# WIFI.net
KiCad netlist of a schematic drawn in Altium Designer
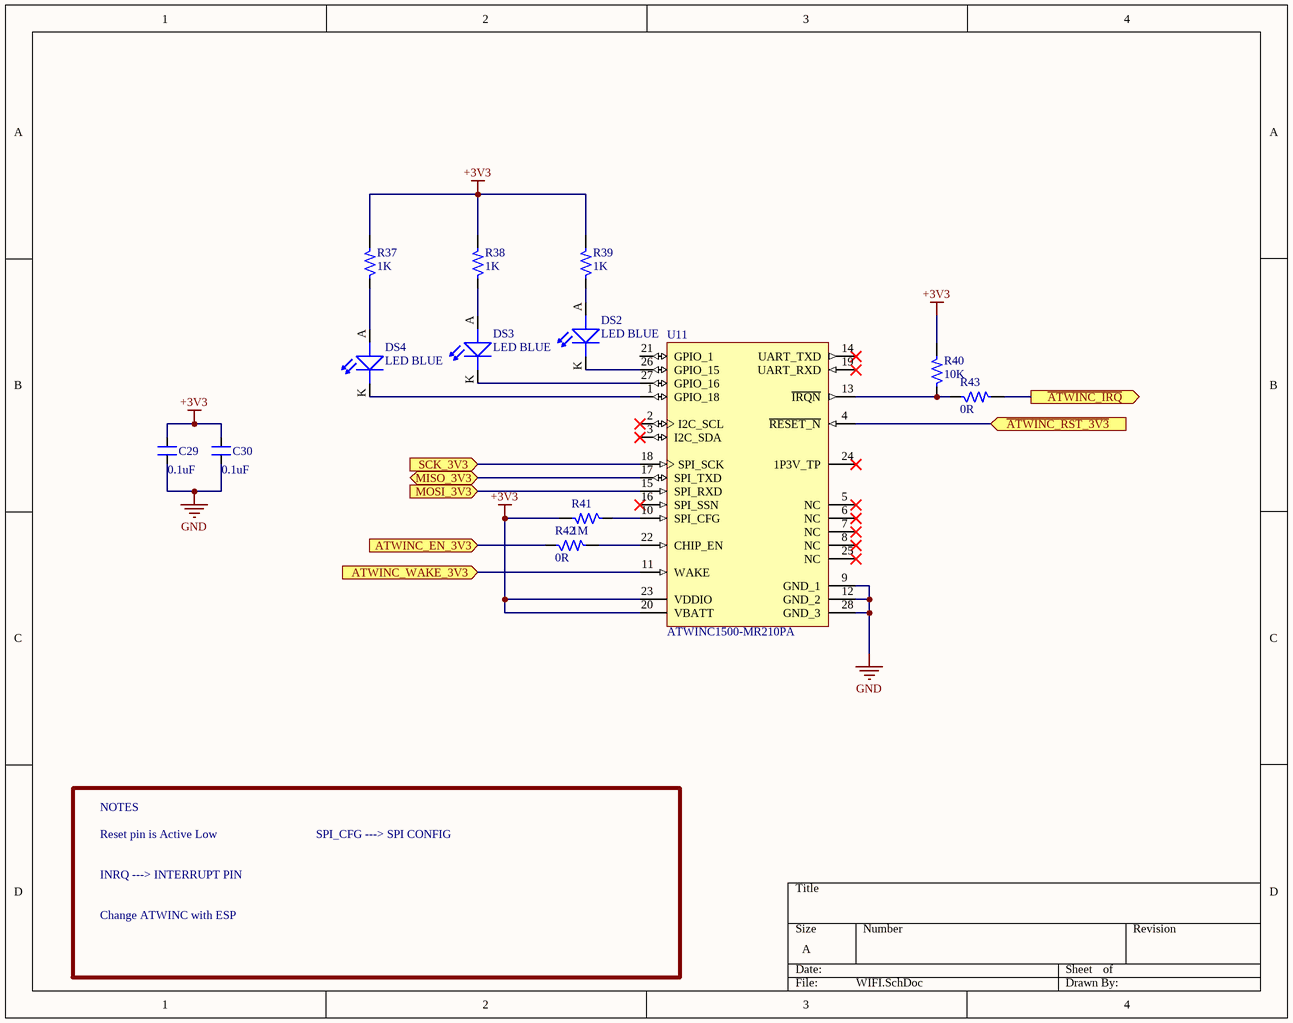
[diagram p0: WIFI.SchDoc]

(export (version "E")
  (design (tool "Eeschema 10.0.6"))
  (components
    (comp (ref "C29")
      (value "0.1uF")
      (footprint "CAP_0805")
      (description "0.1µF ±5% 50V Ceramic Capacitor X7R 0805 (2012 Metric)")
      (fields
        (field (name "MANUFACTURER") "AVX Corporation")
        (field (name "MANUFACTURER PART NUMBER") "08055C104JAT4A")
      )
      (libsource (lib "ESTEEMPCBLIB") (part "CAP_0.1uF-50V-5%-0805"))
    )
    (comp (ref "C30")
      (value "0.1uF")
      (footprint "CAP_0805")
      (description "0.1µF ±5% 50V Ceramic Capacitor X7R 0805 (2012 Metric)")
      (fields
        (field (name "MANUFACTURER") "AVX Corporation")
        (field (name "MANUFACTURER PART NUMBER") "08055C104JAT4A")
      )
      (libsource (lib "ESTEEMPCBLIB") (part "CAP_0.1uF-50V-5%-0805"))
    )
    (comp (ref "DS2")
      (value "LED BLUE")
      (footprint "LED_0805")
      (description "Blue 470nm LED Indication - Discrete 3.3V 0805 (2012 Metric)")
      (fields
        (field (name "MANUFACTURER") "Vishay Lite-On")
        (field (name "MANUFACTURER PART NUMBER") "LTST-C171TBKT")
      )
      (libsource (lib "ESTEEMPCBLIB") (part "LED_BLUE-3V3-20mA-0805"))
    )
    (comp (ref "DS3")
      (value "LED BLUE")
      (footprint "LED_0805")
      (description "Blue 470nm LED Indication - Discrete 3.3V 0805 (2012 Metric)")
      (fields
        (field (name "MANUFACTURER") "Vishay Lite-On")
        (field (name "MANUFACTURER PART NUMBER") "LTST-C171TBKT")
      )
      (libsource (lib "ESTEEMPCBLIB") (part "LED_BLUE-3V3-20mA-0805"))
    )
    (comp (ref "DS4")
      (value "LED BLUE")
      (footprint "LED_0805")
      (description "Blue 470nm LED Indication - Discrete 3.3V 0805 (2012 Metric)")
      (fields
        (field (name "MANUFACTURER") "Vishay Lite-On")
        (field (name "MANUFACTURER PART NUMBER") "LTST-C171TBKT")
      )
      (libsource (lib "ESTEEMPCBLIB") (part "LED_BLUE-3V3-20mA-0805"))
    )
    (comp (ref "R37")
      (value "1K")
      (footprint "RES_0805")
      (description "1 kOhms ±1% 0.125W, 1/8W Chip Resistor 0805 (2012 Metric) Moisture Resistant Thick Film")
      (fields (field (name "MANUFACTURER") "Walsin") (field (name "MANUFACTURER PART NUMBER") "WR08X1001FTL"))
      (libsource (lib "ESTEEMPCBLIB") (part "RES_1K-0.125W-1%-0805"))
    )
    (comp (ref "R38")
      (value "1K")
      (footprint "RES_0805")
      (description "1 kOhms ±1% 0.125W, 1/8W Chip Resistor 0805 (2012 Metric) Moisture Resistant Thick Film")
      (fields (field (name "MANUFACTURER") "Walsin") (field (name "MANUFACTURER PART NUMBER") "WR08X1001FTL"))
      (libsource (lib "ESTEEMPCBLIB") (part "RES_1K-0.125W-1%-0805"))
    )
    (comp (ref "R39")
      (value "1K")
      (footprint "RES_0805")
      (description "1 kOhms ±1% 0.125W, 1/8W Chip Resistor 0805 (2012 Metric) Moisture Resistant Thick Film")
      (fields (field (name "MANUFACTURER") "Walsin") (field (name "MANUFACTURER PART NUMBER") "WR08X1001FTL"))
      (libsource (lib "ESTEEMPCBLIB") (part "RES_1K-0.125W-1%-0805"))
    )
    (comp (ref "R40")
      (value "10K")
      (footprint "RES_0805")
      (description "10 kOhms ±1% 0.125W, 1/8W Chip Resistor 0805 (2012 Metric) Automotive AEC-Q200 Thick Film")
      (fields (field (name "MANUFACTURER") "CTS") (field (name "MANUFACTURER PART NUMBER") "WR08X1002FTL"))
      (libsource (lib "ESTEEMPCBLIB") (part "RES_10K-0.125W-1%-0805"))
    )
    (comp (ref "R41")
      (value "1M")
      (footprint "RES_0805")
      (description "1 MOhms ±1% 0.125W, 1/8W Chip Resistor 0805 (2012 Metric) Automotive AEC-Q200 Thick Film")
      (fields (field (name "MANUFACTURER") "Walsin") (field (name "MANUFACTURER PART NUMBER") "WR08X1004FTL"))
      (libsource (lib "ESTEEMPCBLIB") (part "RES_1M-0.125W-1%-0805"))
    )
    (comp (ref "R42")
      (value "0R")
      (footprint "RES_0805")
      (description "0 Ohms Jumper 0.125W, 1/8W Chip Resistor 0805 (2012 Metric) Automotive AEC-Q200 Thick Film")
      (fields (field (name "MANUFACTURER") "Walsin") (field (name "MANUFACTURER PART NUMBER") "WR08X000PTL"))
      (libsource (lib "ESTEEMPCBLIB") (part "RES_0R-0.125W-1%-0805"))
    )
    (comp (ref "R43")
      (value "0R")
      (footprint "RES_0805")
      (description "0 Ohms Jumper 0.125W, 1/8W Chip Resistor 0805 (2012 Metric) Automotive AEC-Q200 Thick Film")
      (fields (field (name "MANUFACTURER") "Walsin") (field (name "MANUFACTURER PART NUMBER") "WR08X000PTL"))
      (libsource (lib "ESTEEMPCBLIB") (part "RES_0R-0.125W-1%-0805"))
    )
    (comp (ref "U11")
      (value "ATWINC1500-MR210PA")
      (footprint "ATML-ATWINC1500-MR210PA-28_V")
      (description "IEEE 802.11 b/g/n IoT Module, 2.4 GHz, 2.7 to 3.6 V, -40 to 85 degC, 28-Pin Module, RoHS, Tray")
      (fields (field (name "GENERIC PART NUMBER") "ATWINC1500"))
      (libsource (lib "TAREKPCBLIB") (part "ATWINC1500-MR210PA"))
    )
  )
  (nets
    (net (code "1") (name "+3V3") (class "Default")
      (node (ref "C29") (pin "2") (pinfunction "2_2") (pintype "passive"))
      (node (ref "C30") (pin "2") (pinfunction "2_2") (pintype "passive"))
      (node (ref "R37") (pin "2") (pinfunction "2_2") (pintype "passive"))
      (node (ref "R38") (pin "2") (pinfunction "2_2") (pintype "passive"))
      (node (ref "R39") (pin "2") (pinfunction "2_2") (pintype "passive"))
      (node (ref "R40") (pin "2") (pinfunction "2_2") (pintype "passive"))
      (node (ref "R41") (pin "2") (pinfunction "2_2") (pintype "passive"))
      (node (ref "U11") (pin "20") (pinfunction "VBATT_20") (pintype "power_in"))
      (node (ref "U11") (pin "23") (pinfunction "VDDIO_23") (pintype "power_in"))
    )
    (net (code "2") (name "/ATWINC_EN_3V3") (class "Default")
      (node (ref "R42") (pin "1") (pinfunction "1_1") (pintype "passive"))
    )
    (net (code "3") (name "/ATWINC_IRQ") (class "Default")
      (node (ref "R43") (pin "2") (pinfunction "2_2") (pintype "passive"))
    )
    (net (code "4") (name "/ATWINC_RST_3V3") (class "Default")
      (node (ref "U11") (pin "4") (pinfunction "RESET_N_4") (pintype "input"))
    )
    (net (code "5") (name "/ATWINC_WAKE_3V3") (class "Default")
      (node (ref "U11") (pin "11") (pinfunction "WAKE_11") (pintype "input"))
    )
    (net (code "6") (name "/MISO_3V3") (class "Default")
      (node (ref "U11") (pin "17") (pinfunction "SPI_TXD_17") (pintype "bidirectional"))
    )
    (net (code "7") (name "/MOSI_3V3") (class "Default")
      (node (ref "U11") (pin "15") (pinfunction "SPI_RXD_15") (pintype "input"))
    )
    (net (code "8") (name "/SCK_3V3") (class "Default")
      (node (ref "U11") (pin "18") (pinfunction "SPI_SCK_18") (pintype "input"))
    )
    (net (code "9") (name "GND") (class "Default")
      (node (ref "C29") (pin "1") (pinfunction "1_1") (pintype "passive"))
      (node (ref "C30") (pin "1") (pinfunction "1_1") (pintype "passive"))
      (node (ref "U11") (pin "12") (pinfunction "GND_2_12") (pintype "power_in"))
      (node (ref "U11") (pin "28") (pinfunction "GND_3_28") (pintype "power_in"))
      (node (ref "U11") (pin "9") (pinfunction "GND_1_9") (pintype "power_in"))
    )
    (net (code "10") (name "Net-(DS2-ANODE)") (class "Default")
      (node (ref "DS2") (pin "A") (pinfunction "ANODE_A") (pintype "passive"))
      (node (ref "R39") (pin "1") (pinfunction "1_1") (pintype "passive"))
    )
    (net (code "11") (name "Net-(DS2-CATHODE)") (class "Default")
      (node (ref "DS2") (pin "K") (pinfunction "CATHODE_K") (pintype "passive"))
      (node (ref "U11") (pin "26") (pinfunction "GPIO_15_26") (pintype "bidirectional"))
    )
    (net (code "12") (name "Net-(DS3-ANODE)") (class "Default")
      (node (ref "DS3") (pin "A") (pinfunction "ANODE_A") (pintype "passive"))
      (node (ref "R38") (pin "1") (pinfunction "1_1") (pintype "passive"))
    )
    (net (code "13") (name "Net-(DS3-CATHODE)") (class "Default")
      (node (ref "DS3") (pin "K") (pinfunction "CATHODE_K") (pintype "passive"))
      (node (ref "U11") (pin "27") (pinfunction "GPIO_16_27") (pintype "bidirectional"))
    )
    (net (code "14") (name "Net-(DS4-ANODE)") (class "Default")
      (node (ref "DS4") (pin "A") (pinfunction "ANODE_A") (pintype "passive"))
      (node (ref "R37") (pin "1") (pinfunction "1_1") (pintype "passive"))
    )
    (net (code "15") (name "Net-(DS4-CATHODE)") (class "Default")
      (node (ref "DS4") (pin "K") (pinfunction "CATHODE_K") (pintype "passive"))
      (node (ref "U11") (pin "1") (pinfunction "GPIO_18_1") (pintype "bidirectional"))
    )
    (net (code "16") (name "Net-(U11-CHIP_EN)") (class "Default")
      (node (ref "R42") (pin "2") (pinfunction "2_2") (pintype "passive"))
      (node (ref "U11") (pin "22") (pinfunction "CHIP_EN_22") (pintype "input"))
    )
    (net (code "17") (name "Net-(U11-IRQN)") (class "Default")
      (node (ref "R40") (pin "1") (pinfunction "1_1") (pintype "passive"))
      (node (ref "R43") (pin "1") (pinfunction "1_1") (pintype "passive"))
      (node (ref "U11") (pin "13") (pinfunction "IRQN_13") (pintype "output"))
    )
    (net (code "18") (name "Net-(U11-SPI_CFG)") (class "Default")
      (node (ref "R41") (pin "1") (pinfunction "1_1") (pintype "passive"))
      (node (ref "U11") (pin "10") (pinfunction "SPI_CFG_10") (pintype "input"))
    )
    (net (code "19") (name "unconnected-(U11-1P3V_TP-Pad24)") (class "Default")
      (node (ref "U11") (pin "24") (pinfunction "1P3V_TP_24") (pintype "passive+no_connect"))
    )
    (net (code "20") (name "unconnected-(U11-GPIO_1-Pad21)") (class "Default")
      (node (ref "U11") (pin "21") (pinfunction "GPIO_1_21") (pintype "bidirectional"))
    )
    (net (code "21") (name "unconnected-(U11-I2C_SCL-Pad2)") (class "Default")
      (node (ref "U11") (pin "2") (pinfunction "I2C_SCL_2") (pintype "bidirectional+no_connect"))
    )
    (net (code "22") (name "unconnected-(U11-I2C_SDA-Pad3)") (class "Default")
      (node (ref "U11") (pin "3") (pinfunction "I2C_SDA_3") (pintype "bidirectional+no_connect"))
    )
    (net (code "23") (name "unconnected-(U11-NC-Pad5)") (class "Default")
      (node (ref "U11") (pin "5") (pinfunction "NC_5") (pintype "passive+no_connect"))
    )
    (net (code "24") (name "unconnected-(U11-NC-Pad6)") (class "Default")
      (node (ref "U11") (pin "6") (pinfunction "NC_6") (pintype "passive+no_connect"))
    )
    (net (code "25") (name "unconnected-(U11-NC-Pad7)") (class "Default")
      (node (ref "U11") (pin "7") (pinfunction "NC_7") (pintype "passive+no_connect"))
    )
    (net (code "26") (name "unconnected-(U11-NC-Pad8)") (class "Default")
      (node (ref "U11") (pin "8") (pinfunction "NC_8") (pintype "passive+no_connect"))
    )
    (net (code "27") (name "unconnected-(U11-NC-Pad25)") (class "Default")
      (node (ref "U11") (pin "25") (pinfunction "NC_25") (pintype "passive+no_connect"))
    )
    (net (code "28") (name "unconnected-(U11-SPI_SSN-Pad16)") (class "Default")
      (node (ref "U11") (pin "16") (pinfunction "SPI_SSN_16") (pintype "input+no_connect"))
    )
    (net (code "29") (name "unconnected-(U11-UART_RXD-Pad19)") (class "Default")
      (node (ref "U11") (pin "19") (pinfunction "UART_RXD_19") (pintype "input+no_connect"))
    )
    (net (code "30") (name "unconnected-(U11-UART_TXD-Pad14)") (class "Default")
      (node (ref "U11") (pin "14") (pinfunction "UART_TXD_14") (pintype "output+no_connect"))
    )
  )
)
